# 0X_-_CPU_-_DISP_CSI.net
KiCad netlist of a schematic drawn in Altium Designer
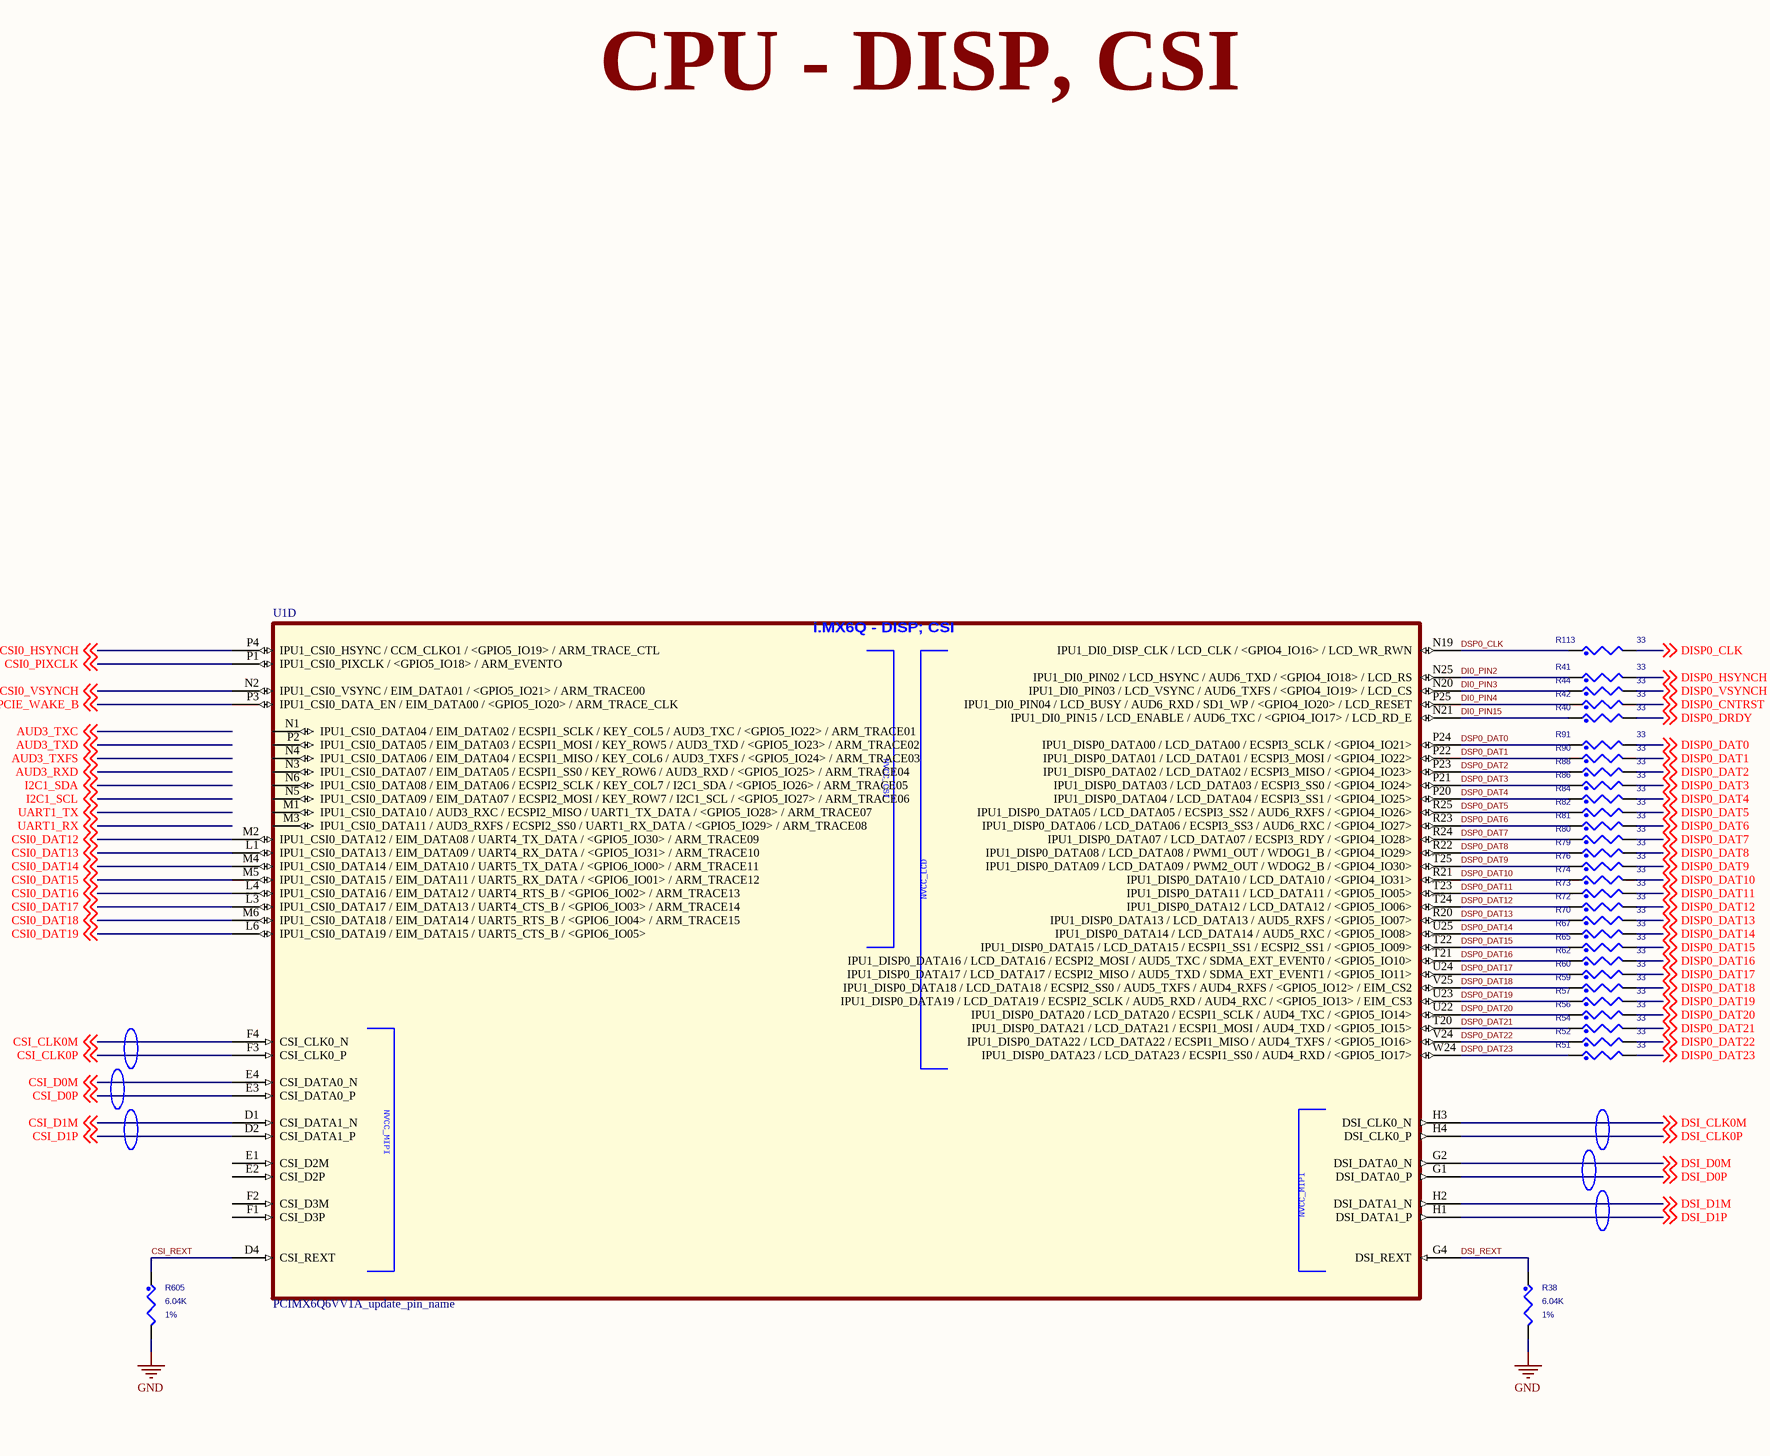
[diagram p0: [0X] - CPU - DISP, CSI.SchDoc, left]
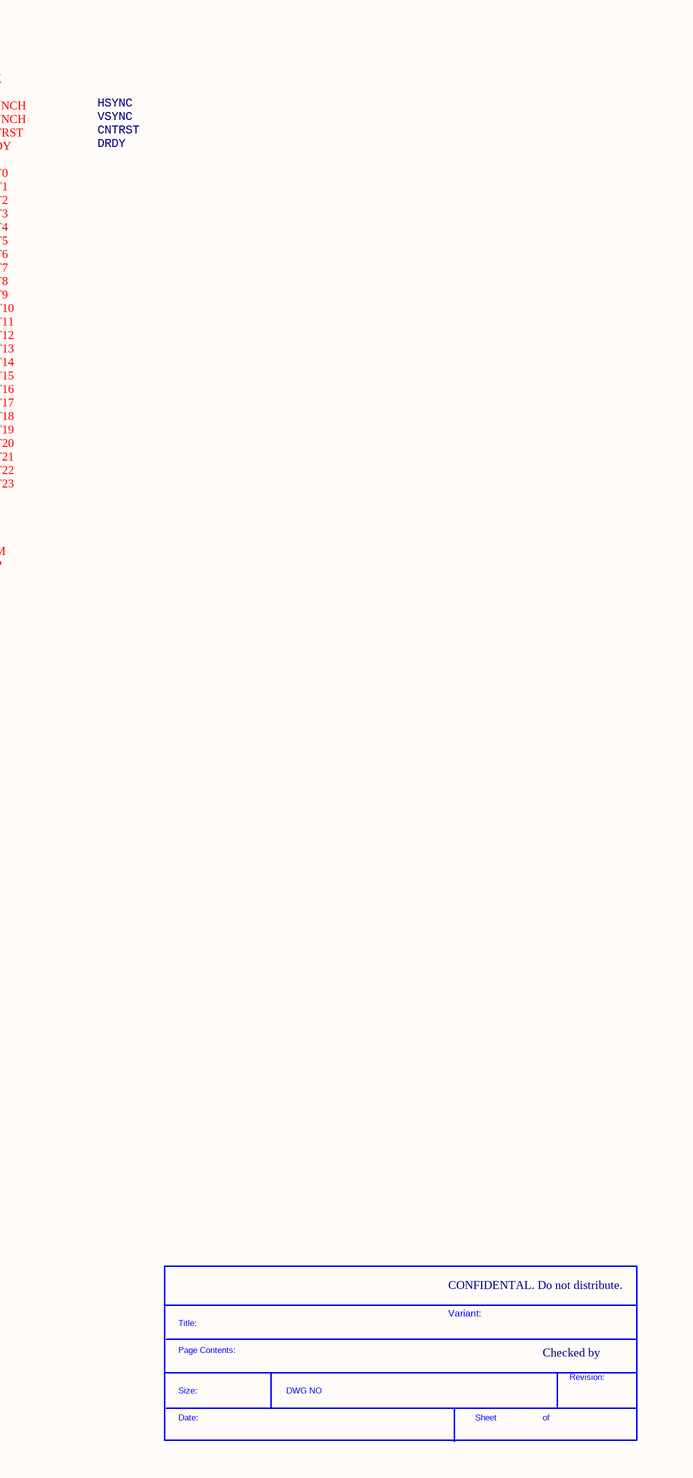
[diagram p1: [0X] - CPU - DISP, CSI.SchDoc, right]

(export (version "E")
  (design (tool "Eeschema 10.0.6"))
  (components
    (comp (ref "*") (value "SDTitleBlock") (libsource (lib "*") (part "SDTitleBlock")))
    (comp (ref "R38")
      (value "6.04K")
      (description "RES MF 6.04K  1/16W 1% 0402")
      (fields (field (name "TOLERANCE") "1%"))
      (libsource (lib "*") (part "RES"))
    )
    (comp (ref "R40")
      (value "33")
      (description "RES MF 33 OHM 1/16W 5% 0402")
      (fields (field (name "TOLERANCE") "5%"))
      (libsource (lib "*") (part "RES"))
    )
    (comp (ref "R41")
      (value "33")
      (description "RES MF 33 OHM 1/16W 5% 0402")
      (fields (field (name "TOLERANCE") "5%"))
      (libsource (lib "*") (part "RES"))
    )
    (comp (ref "R42")
      (value "33")
      (description "RES MF 33 OHM 1/16W 5% 0402")
      (fields (field (name "TOLERANCE") "5%"))
      (libsource (lib "*") (part "RES"))
    )
    (comp (ref "R44")
      (value "33")
      (description "RES MF 33 OHM 1/16W 5% 0402")
      (fields (field (name "TOLERANCE") "5%"))
      (libsource (lib "*") (part "RES"))
    )
    (comp (ref "R51")
      (value "33")
      (description "RES MF 33 OHM 1/16W 5% 0402")
      (fields (field (name "TOLERANCE") "5%"))
      (libsource (lib "*") (part "RES"))
    )
    (comp (ref "R52")
      (value "33")
      (description "RES MF 33 OHM 1/16W 5% 0402")
      (fields (field (name "TOLERANCE") "5%"))
      (libsource (lib "*") (part "RES"))
    )
    (comp (ref "R54")
      (value "33")
      (description "RES MF 33 OHM 1/16W 5% 0402")
      (fields (field (name "TOLERANCE") "5%"))
      (libsource (lib "*") (part "RES"))
    )
    (comp (ref "R56")
      (value "33")
      (description "RES MF 33 OHM 1/16W 5% 0402")
      (fields (field (name "TOLERANCE") "5%"))
      (libsource (lib "*") (part "RES"))
    )
    (comp (ref "R57")
      (value "33")
      (description "RES MF 33 OHM 1/16W 5% 0402")
      (fields (field (name "TOLERANCE") "5%"))
      (libsource (lib "*") (part "RES"))
    )
    (comp (ref "R59")
      (value "33")
      (description "RES MF 33 OHM 1/16W 5% 0402")
      (fields (field (name "TOLERANCE") "5%"))
      (libsource (lib "*") (part "RES"))
    )
    (comp (ref "R60")
      (value "33")
      (description "RES MF 33 OHM 1/16W 5% 0402")
      (fields (field (name "TOLERANCE") "5%"))
      (libsource (lib "*") (part "RES"))
    )
    (comp (ref "R62")
      (value "33")
      (description "RES MF 33 OHM 1/16W 5% 0402")
      (fields (field (name "TOLERANCE") "5%"))
      (libsource (lib "*") (part "RES"))
    )
    (comp (ref "R65")
      (value "33")
      (description "RES MF 33 OHM 1/16W 5% 0402")
      (fields (field (name "TOLERANCE") "5%"))
      (libsource (lib "*") (part "RES"))
    )
    (comp (ref "R67")
      (value "33")
      (description "RES MF 33 OHM 1/16W 5% 0402")
      (fields (field (name "TOLERANCE") "5%"))
      (libsource (lib "*") (part "RES"))
    )
    (comp (ref "R70")
      (value "33")
      (description "RES MF 33 OHM 1/16W 5% 0402")
      (fields (field (name "TOLERANCE") "5%"))
      (libsource (lib "*") (part "RES"))
    )
    (comp (ref "R72")
      (value "33")
      (description "RES MF 33 OHM 1/16W 5% 0402")
      (fields (field (name "TOLERANCE") "5%"))
      (libsource (lib "*") (part "RES"))
    )
    (comp (ref "R73")
      (value "33")
      (description "RES MF 33 OHM 1/16W 5% 0402")
      (fields (field (name "TOLERANCE") "5%"))
      (libsource (lib "*") (part "RES"))
    )
    (comp (ref "R74")
      (value "33")
      (description "RES MF 33 OHM 1/16W 5% 0402")
      (fields (field (name "TOLERANCE") "5%"))
      (libsource (lib "*") (part "RES"))
    )
    (comp (ref "R76")
      (value "33")
      (description "RES MF 33 OHM 1/16W 5% 0402")
      (fields (field (name "TOLERANCE") "5%"))
      (libsource (lib "*") (part "RES"))
    )
    (comp (ref "R79")
      (value "33")
      (description "RES MF 33 OHM 1/16W 5% 0402")
      (fields (field (name "TOLERANCE") "5%"))
      (libsource (lib "*") (part "RES"))
    )
    (comp (ref "R80")
      (value "33")
      (description "RES MF 33 OHM 1/16W 5% 0402")
      (fields (field (name "TOLERANCE") "5%"))
      (libsource (lib "*") (part "RES"))
    )
    (comp (ref "R81")
      (value "33")
      (description "RES MF 33 OHM 1/16W 5% 0402")
      (fields (field (name "TOLERANCE") "5%"))
      (libsource (lib "*") (part "RES"))
    )
    (comp (ref "R82")
      (value "33")
      (description "RES MF 33 OHM 1/16W 5% 0402")
      (fields (field (name "TOLERANCE") "5%"))
      (libsource (lib "*") (part "RES"))
    )
    (comp (ref "R84")
      (value "33")
      (description "RES MF 33 OHM 1/16W 5% 0402")
      (fields (field (name "TOLERANCE") "5%"))
      (libsource (lib "*") (part "RES"))
    )
    (comp (ref "R86")
      (value "33")
      (description "RES MF 33 OHM 1/16W 5% 0402")
      (fields (field (name "TOLERANCE") "5%"))
      (libsource (lib "*") (part "RES"))
    )
    (comp (ref "R88")
      (value "33")
      (description "RES MF 33 OHM 1/16W 5% 0402")
      (fields (field (name "TOLERANCE") "5%"))
      (libsource (lib "*") (part "RES"))
    )
    (comp (ref "R90")
      (value "33")
      (description "RES MF 33 OHM 1/16W 5% 0402")
      (fields (field (name "TOLERANCE") "5%"))
      (libsource (lib "*") (part "RES"))
    )
    (comp (ref "R91")
      (value "33")
      (description "RES MF 33 OHM 1/16W 5% 0402")
      (fields (field (name "TOLERANCE") "5%"))
      (libsource (lib "*") (part "RES"))
    )
    (comp (ref "R113")
      (value "33")
      (description "RES MF 33 OHM 1/16W 5% 0402")
      (fields (field (name "TOLERANCE") "5%"))
      (libsource (lib "*") (part "RES"))
    )
    (comp (ref "R605")
      (value "6.04K")
      (description "RES MF 6.04K  1/16W 1% 0402")
      (fields (field (name "TOLERANCE") "1%"))
      (libsource (lib "*") (part "RES"))
    )
    (comp (ref "U1")
      (value "PCIMX6Q6VV1A_update_pin_name")
      (libsource (lib "SCH-27516_C3_16_2_Library") (part "PCIMX6Q6VV1A_update_pin_name"))
    )
  )
  (nets
    (net (code "1") (name "/CSI_REXT") (class "Default")
      (node (ref "R605") (pin "1") (pinfunction "1_1") (pintype "passive"))
      (node (ref "U1") (pin "D4") (pinfunction "CSI_REXT_D4") (pintype "input"))
    )
    (net (code "2") (name "/DI0_PIN2") (class "Default")
      (node (ref "R41") (pin "1") (pinfunction "1_1") (pintype "passive"))
      (node (ref "U1") (pin "N25") (pinfunction "IPU1_DI0_PIN02_/_LCD_HSYNC_/_AUD6_TXD_/_<GPIO4_IO18>_/_LCD_RS_N25") (pintype "bidirectional"))
    )
    (net (code "3") (name "/DI0_PIN3") (class "Default")
      (node (ref "R44") (pin "1") (pinfunction "1_1") (pintype "passive"))
      (node (ref "U1") (pin "N20") (pinfunction "IPU1_DI0_PIN03_/_LCD_VSYNC_/_AUD6_TXFS_/_<GPIO4_IO19>_/_LCD_CS_N20") (pintype "bidirectional"))
    )
    (net (code "4") (name "/DI0_PIN4") (class "Default")
      (node (ref "R42") (pin "1") (pinfunction "1_1") (pintype "passive"))
      (node (ref "U1") (pin "P25") (pinfunction "IPU1_DI0_PIN04_/_LCD_BUSY_/_AUD6_RXD_/_SD1_WP_/_<GPIO4_IO20>_/_LCD_RESET_P25") (pintype "bidirectional"))
    )
    (net (code "5") (name "/DI0_PIN15") (class "Default")
      (node (ref "R40") (pin "1") (pinfunction "1_1") (pintype "passive"))
      (node (ref "U1") (pin "N21") (pinfunction "IPU1_DI0_PIN15_/_LCD_ENABLE_/_AUD6_TXC_/_<GPIO4_IO17>_/_LCD_RD_E_N21") (pintype "bidirectional"))
    )
    (net (code "6") (name "/DSI_REXT") (class "Default")
      (node (ref "R38") (pin "1") (pinfunction "1_1") (pintype "passive"))
      (node (ref "U1") (pin "G4") (pinfunction "DSI_REXT_G4") (pintype "input"))
    )
    (net (code "7") (name "/DSP0_CLK") (class "Default")
      (node (ref "R113") (pin "1") (pinfunction "1_1") (pintype "passive"))
      (node (ref "U1") (pin "N19") (pinfunction "IPU1_DI0_DISP_CLK_/_LCD_CLK_/_<GPIO4_IO16>_/_LCD_WR_RWN_N19") (pintype "bidirectional"))
    )
    (net (code "8") (name "/DSP0_DAT0") (class "Default")
      (node (ref "R91") (pin "1") (pinfunction "1_1") (pintype "passive"))
      (node (ref "U1") (pin "P24") (pinfunction "IPU1_DISP0_DATA00_/_LCD_DATA00_/_ECSPI3_SCLK_/_<GPIO4_IO21>_P24") (pintype "bidirectional"))
    )
    (net (code "9") (name "/DSP0_DAT1") (class "Default")
      (node (ref "R90") (pin "1") (pinfunction "1_1") (pintype "passive"))
      (node (ref "U1") (pin "P22") (pinfunction "IPU1_DISP0_DATA01_/_LCD_DATA01_/_ECSPI3_MOSI_/_<GPIO4_IO22>_P22") (pintype "bidirectional"))
    )
    (net (code "10") (name "/DSP0_DAT2") (class "Default")
      (node (ref "R88") (pin "1") (pinfunction "1_1") (pintype "passive"))
      (node (ref "U1") (pin "P23") (pinfunction "IPU1_DISP0_DATA02_/_LCD_DATA02_/_ECSPI3_MISO_/_<GPIO4_IO23>_P23") (pintype "bidirectional"))
    )
    (net (code "11") (name "/DSP0_DAT3") (class "Default")
      (node (ref "R86") (pin "1") (pinfunction "1_1") (pintype "passive"))
      (node (ref "U1") (pin "P21") (pinfunction "IPU1_DISP0_DATA03_/_LCD_DATA03_/_ECSPI3_SS0_/_<GPIO4_IO24>_P21") (pintype "bidirectional"))
    )
    (net (code "12") (name "/DSP0_DAT4") (class "Default")
      (node (ref "R84") (pin "1") (pinfunction "1_1") (pintype "passive"))
      (node (ref "U1") (pin "P20") (pinfunction "IPU1_DISP0_DATA04_/_LCD_DATA04_/_ECSPI3_SS1_/_<GPIO4_IO25>_P20") (pintype "bidirectional"))
    )
    (net (code "13") (name "/DSP0_DAT5") (class "Default")
      (node (ref "R82") (pin "1") (pinfunction "1_1") (pintype "passive"))
      (node (ref "U1") (pin "R25") (pinfunction "IPU1_DISP0_DATA05_/_LCD_DATA05_/_ECSPI3_SS2_/_AUD6_RXFS_/_<GPIO4_IO26>_R25") (pintype "bidirectional"))
    )
    (net (code "14") (name "/DSP0_DAT6") (class "Default")
      (node (ref "R81") (pin "1") (pinfunction "1_1") (pintype "passive"))
      (node (ref "U1") (pin "R23") (pinfunction "IPU1_DISP0_DATA06_/_LCD_DATA06_/_ECSPI3_SS3_/_AUD6_RXC_/_<GPIO4_IO27>_R23") (pintype "bidirectional"))
    )
    (net (code "15") (name "/DSP0_DAT7") (class "Default")
      (node (ref "R80") (pin "1") (pinfunction "1_1") (pintype "passive"))
      (node (ref "U1") (pin "R24") (pinfunction "IPU1_DISP0_DATA07_/_LCD_DATA07_/_ECSPI3_RDY_/_<GPIO4_IO28>_R24") (pintype "bidirectional"))
    )
    (net (code "16") (name "/DSP0_DAT8") (class "Default")
      (node (ref "R79") (pin "1") (pinfunction "1_1") (pintype "passive"))
      (node (ref "U1") (pin "R22") (pinfunction "IPU1_DISP0_DATA08_/_LCD_DATA08_/_PWM1_OUT_/_WDOG1_B_/_<GPIO4_IO29>_R22") (pintype "bidirectional"))
    )
    (net (code "17") (name "/DSP0_DAT9") (class "Default")
      (node (ref "R76") (pin "1") (pinfunction "1_1") (pintype "passive"))
      (node (ref "U1") (pin "T25") (pinfunction "IPU1_DISP0_DATA09_/_LCD_DATA09_/_PWM2_OUT_/_WDOG2_B_/_<GPIO4_IO30>_T25") (pintype "bidirectional"))
    )
    (net (code "18") (name "/DSP0_DAT10") (class "Default")
      (node (ref "R74") (pin "1") (pinfunction "1_1") (pintype "passive"))
      (node (ref "U1") (pin "R21") (pinfunction "IPU1_DISP0_DATA10_/_LCD_DATA10_/_<GPIO4_IO31>_R21") (pintype "bidirectional"))
    )
    (net (code "19") (name "/DSP0_DAT11") (class "Default")
      (node (ref "R73") (pin "1") (pinfunction "1_1") (pintype "passive"))
      (node (ref "U1") (pin "T23") (pinfunction "IPU1_DISP0_DATA11_/_LCD_DATA11_/_<GPIO5_IO05>_T23") (pintype "bidirectional"))
    )
    (net (code "20") (name "/DSP0_DAT12") (class "Default")
      (node (ref "R72") (pin "1") (pinfunction "1_1") (pintype "passive"))
      (node (ref "U1") (pin "T24") (pinfunction "IPU1_DISP0_DATA12_/_LCD_DATA12_/_<GPIO5_IO06>_T24") (pintype "bidirectional"))
    )
    (net (code "21") (name "/DSP0_DAT13") (class "Default")
      (node (ref "R70") (pin "1") (pinfunction "1_1") (pintype "passive"))
      (node (ref "U1") (pin "R20") (pinfunction "IPU1_DISP0_DATA13_/_LCD_DATA13_/_AUD5_RXFS_/_<GPIO5_IO07>_R20") (pintype "bidirectional"))
    )
    (net (code "22") (name "/DSP0_DAT14") (class "Default")
      (node (ref "R67") (pin "1") (pinfunction "1_1") (pintype "passive"))
      (node (ref "U1") (pin "U25") (pinfunction "IPU1_DISP0_DATA14_/_LCD_DATA14_/_AUD5_RXC_/_<GPIO5_IO08>_U25") (pintype "bidirectional"))
    )
    (net (code "23") (name "/DSP0_DAT15") (class "Default")
      (node (ref "R65") (pin "1") (pinfunction "1_1") (pintype "passive"))
      (node (ref "U1") (pin "T22") (pinfunction "IPU1_DISP0_DATA15_/_LCD_DATA15_/_ECSPI1_SS1_/_ECSPI2_SS1_/_<GPIO5_IO09>_T22") (pintype "bidirectional"))
    )
    (net (code "24") (name "/DSP0_DAT16") (class "Default")
      (node (ref "R62") (pin "1") (pinfunction "1_1") (pintype "passive"))
      (node (ref "U1") (pin "T21") (pinfunction "IPU1_DISP0_DATA16_/_LCD_DATA16_/_ECSPI2_MOSI_/_AUD5_TXC_/_SDMA_EXT_EVENT0_/_<GPIO5_IO10>_T21") (pintype "bidirectional"))
    )
    (net (code "25") (name "/DSP0_DAT17") (class "Default")
      (node (ref "R60") (pin "1") (pinfunction "1_1") (pintype "passive"))
      (node (ref "U1") (pin "U24") (pinfunction "IPU1_DISP0_DATA17_/_LCD_DATA17_/_ECSPI2_MISO_/_AUD5_TXD_/_SDMA_EXT_EVENT1_/_<GPIO5_IO11>_U24") (pintype "bidirectional"))
    )
    (net (code "26") (name "/DSP0_DAT18") (class "Default")
      (node (ref "R59") (pin "1") (pinfunction "1_1") (pintype "passive"))
      (node (ref "U1") (pin "V25") (pinfunction "IPU1_DISP0_DATA18_/_LCD_DATA18_/_ECSPI2_SS0_/_AUD5_TXFS_/_AUD4_RXFS_/_<GPIO5_IO12>_/_EIM_CS2_V25") (pintype "bidirectional"))
    )
    (net (code "27") (name "/DSP0_DAT19") (class "Default")
      (node (ref "R57") (pin "1") (pinfunction "1_1") (pintype "passive"))
      (node (ref "U1") (pin "U23") (pinfunction "IPU1_DISP0_DATA19_/_LCD_DATA19_/_ECSPI2_SCLK_/_AUD5_RXD_/_AUD4_RXC_/_<GPIO5_IO13>_/_EIM_CS3_U23") (pintype "bidirectional"))
    )
    (net (code "28") (name "/DSP0_DAT20") (class "Default")
      (node (ref "R56") (pin "1") (pinfunction "1_1") (pintype "passive"))
      (node (ref "U1") (pin "U22") (pinfunction "IPU1_DISP0_DATA20_/_LCD_DATA20_/_ECSPI1_SCLK_/_AUD4_TXC_/_<GPIO5_IO14>_U22") (pintype "bidirectional"))
    )
    (net (code "29") (name "/DSP0_DAT21") (class "Default")
      (node (ref "R54") (pin "1") (pinfunction "1_1") (pintype "passive"))
      (node (ref "U1") (pin "T20") (pinfunction "IPU1_DISP0_DATA21_/_LCD_DATA21_/_ECSPI1_MOSI_/_AUD4_TXD_/_<GPIO5_IO15>_T20") (pintype "bidirectional"))
    )
    (net (code "30") (name "/DSP0_DAT22") (class "Default")
      (node (ref "R52") (pin "1") (pinfunction "1_1") (pintype "passive"))
      (node (ref "U1") (pin "V24") (pinfunction "IPU1_DISP0_DATA22_/_LCD_DATA22_/_ECSPI1_MISO_/_AUD4_TXFS_/_<GPIO5_IO16>_V24") (pintype "bidirectional"))
    )
    (net (code "31") (name "/DSP0_DAT23") (class "Default")
      (node (ref "R51") (pin "1") (pinfunction "1_1") (pintype "passive"))
      (node (ref "U1") (pin "W24") (pinfunction "IPU1_DISP0_DATA23_/_LCD_DATA23_/_ECSPI1_SS0_/_AUD4_RXD_/_<GPIO5_IO17>_W24") (pintype "bidirectional"))
    )
    (net (code "36") (name "CSI0_DAT12") (class "Default")
      (node (ref "U1") (pin "M2") (pinfunction "IPU1_CSI0_DATA12_/_EIM_DATA08_/_UART4_TX_DATA_/_<GPIO5_IO30>_/_ARM_TRACE09_M2") (pintype "bidirectional"))
    )
    (net (code "37") (name "CSI0_DAT13") (class "Default")
      (node (ref "U1") (pin "L1") (pinfunction "IPU1_CSI0_DATA13_/_EIM_DATA09_/_UART4_RX_DATA_/_<GPIO5_IO31>_/_ARM_TRACE10_L1") (pintype "bidirectional"))
    )
    (net (code "38") (name "CSI0_DAT14") (class "Default")
      (node (ref "U1") (pin "M4") (pinfunction "IPU1_CSI0_DATA14_/_EIM_DATA10_/_UART5_TX_DATA_/_<GPIO6_IO00>_/_ARM_TRACE11_M4") (pintype "bidirectional"))
    )
    (net (code "39") (name "CSI0_DAT15") (class "Default")
      (node (ref "U1") (pin "M5") (pinfunction "IPU1_CSI0_DATA15_/_EIM_DATA11_/_UART5_RX_DATA_/_<GPIO6_IO01>_/_ARM_TRACE12_M5") (pintype "bidirectional"))
    )
    (net (code "40") (name "CSI0_DAT16") (class "Default")
      (node (ref "U1") (pin "L4") (pinfunction "IPU1_CSI0_DATA16_/_EIM_DATA12_/_UART4_RTS_B_/_<GPIO6_IO02>_/_ARM_TRACE13_L4") (pintype "bidirectional"))
    )
    (net (code "41") (name "CSI0_DAT17") (class "Default")
      (node (ref "U1") (pin "L3") (pinfunction "IPU1_CSI0_DATA17_/_EIM_DATA13_/_UART4_CTS_B_/_<GPIO6_IO03>_/_ARM_TRACE14_L3") (pintype "bidirectional"))
    )
    (net (code "42") (name "CSI0_DAT18") (class "Default")
      (node (ref "U1") (pin "M6") (pinfunction "IPU1_CSI0_DATA18_/_EIM_DATA14_/_UART5_RTS_B_/_<GPIO6_IO04>_/_ARM_TRACE15_M6") (pintype "bidirectional"))
    )
    (net (code "43") (name "CSI0_DAT19") (class "Default")
      (node (ref "U1") (pin "L6") (pinfunction "IPU1_CSI0_DATA19_/_EIM_DATA15_/_UART5_CTS_B_/_<GPIO6_IO05>_L6") (pintype "bidirectional"))
    )
    (net (code "44") (name "CSI0_HSYNCH") (class "Default")
      (node (ref "U1") (pin "P4") (pinfunction "IPU1_CSI0_HSYNC_/_CCM_CLKO1_/_<GPIO5_IO19>_/_ARM_TRACE_CTL_P4") (pintype "bidirectional"))
    )
    (net (code "45") (name "CSI0_PIXCLK") (class "Default")
      (node (ref "U1") (pin "P1") (pinfunction "IPU1_CSI0_PIXCLK_/_<GPIO5_IO18>_/_ARM_EVENTO_P1") (pintype "bidirectional"))
    )
    (net (code "46") (name "CSI0_VSYNCH") (class "Default")
      (node (ref "U1") (pin "N2") (pinfunction "IPU1_CSI0_VSYNC_/_EIM_DATA01_/_<GPIO5_IO21>_/_ARM_TRACE00_N2") (pintype "bidirectional"))
    )
    (net (code "47") (name "CSI_CLK0M") (class "Default")
      (node (ref "U1") (pin "F4") (pinfunction "CSI_CLK0_N_F4") (pintype "input"))
    )
    (net (code "48") (name "CSI_CLK0P") (class "Default")
      (node (ref "U1") (pin "F3") (pinfunction "CSI_CLK0_P_F3") (pintype "input"))
    )
    (net (code "49") (name "CSI_D0M") (class "Default")
      (node (ref "U1") (pin "E4") (pinfunction "CSI_DATA0_N_E4") (pintype "input"))
    )
    (net (code "50") (name "CSI_D0P") (class "Default")
      (node (ref "U1") (pin "E3") (pinfunction "CSI_DATA0_P_E3") (pintype "input"))
    )
    (net (code "51") (name "CSI_D1M") (class "Default")
      (node (ref "U1") (pin "D1") (pinfunction "CSI_DATA1_N_D1") (pintype "input"))
    )
    (net (code "52") (name "CSI_D1P") (class "Default")
      (node (ref "U1") (pin "D2") (pinfunction "CSI_DATA1_P_D2") (pintype "input"))
    )
    (net (code "53") (name "DISP0_CLK") (class "Default")
      (node (ref "R113") (pin "2") (pinfunction "2_2") (pintype "passive"))
    )
    (net (code "54") (name "DISP0_CNTRST") (class "Default")
      (node (ref "R42") (pin "2") (pinfunction "2_2") (pintype "passive"))
    )
    (net (code "55") (name "DISP0_DAT0") (class "Default")
      (node (ref "R91") (pin "2") (pinfunction "2_2") (pintype "passive"))
    )
    (net (code "56") (name "DISP0_DAT1") (class "Default")
      (node (ref "R90") (pin "2") (pinfunction "2_2") (pintype "passive"))
    )
    (net (code "57") (name "DISP0_DAT2") (class "Default")
      (node (ref "R88") (pin "2") (pinfunction "2_2") (pintype "passive"))
    )
    (net (code "58") (name "DISP0_DAT3") (class "Default")
      (node (ref "R86") (pin "2") (pinfunction "2_2") (pintype "passive"))
    )
    (net (code "59") (name "DISP0_DAT4") (class "Default")
      (node (ref "R84") (pin "2") (pinfunction "2_2") (pintype "passive"))
    )
    (net (code "60") (name "DISP0_DAT5") (class "Default")
      (node (ref "R82") (pin "2") (pinfunction "2_2") (pintype "passive"))
    )
    (net (code "61") (name "DISP0_DAT6") (class "Default")
      (node (ref "R81") (pin "2") (pinfunction "2_2") (pintype "passive"))
    )
    (net (code "62") (name "DISP0_DAT7") (class "Default")
      (node (ref "R80") (pin "2") (pinfunction "2_2") (pintype "passive"))
    )
    (net (code "63") (name "DISP0_DAT8") (class "Default")
      (node (ref "R79") (pin "2") (pinfunction "2_2") (pintype "passive"))
    )
    (net (code "64") (name "DISP0_DAT9") (class "Default")
      (node (ref "R76") (pin "2") (pinfunction "2_2") (pintype "passive"))
    )
    (net (code "65") (name "DISP0_DAT10") (class "Default")
      (node (ref "R74") (pin "2") (pinfunction "2_2") (pintype "passive"))
    )
    (net (code "66") (name "DISP0_DAT11") (class "Default")
      (node (ref "R73") (pin "2") (pinfunction "2_2") (pintype "passive"))
    )
    (net (code "67") (name "DISP0_DAT12") (class "Default")
      (node (ref "R72") (pin "2") (pinfunction "2_2") (pintype "passive"))
    )
    (net (code "68") (name "DISP0_DAT13") (class "Default")
      (node (ref "R70") (pin "2") (pinfunction "2_2") (pintype "passive"))
    )
    (net (code "69") (name "DISP0_DAT14") (class "Default")
      (node (ref "R67") (pin "2") (pinfunction "2_2") (pintype "passive"))
    )
    (net (code "70") (name "DISP0_DAT15") (class "Default")
      (node (ref "R65") (pin "2") (pinfunction "2_2") (pintype "passive"))
    )
    (net (code "71") (name "DISP0_DAT16") (class "Default")
      (node (ref "R62") (pin "2") (pinfunction "2_2") (pintype "passive"))
    )
    (net (code "72") (name "DISP0_DAT17") (class "Default")
      (node (ref "R60") (pin "2") (pinfunction "2_2") (pintype "passive"))
    )
    (net (code "73") (name "DISP0_DAT18") (class "Default")
      (node (ref "R59") (pin "2") (pinfunction "2_2") (pintype "passive"))
    )
    (net (code "74") (name "DISP0_DAT19") (class "Default")
      (node (ref "R57") (pin "2") (pinfunction "2_2") (pintype "passive"))
    )
    (net (code "75") (name "DISP0_DAT20") (class "Default")
      (node (ref "R56") (pin "2") (pinfunction "2_2") (pintype "passive"))
    )
    (net (code "76") (name "DISP0_DAT21") (class "Default")
      (node (ref "R54") (pin "2") (pinfunction "2_2") (pintype "passive"))
    )
    (net (code "77") (name "DISP0_DAT22") (class "Default")
      (node (ref "R52") (pin "2") (pinfunction "2_2") (pintype "passive"))
    )
    (net (code "78") (name "DISP0_DAT23") (class "Default")
      (node (ref "R51") (pin "2") (pinfunction "2_2") (pintype "passive"))
    )
    (net (code "79") (name "DISP0_DRDY") (class "Default")
      (node (ref "R40") (pin "2") (pinfunction "2_2") (pintype "passive"))
    )
    (net (code "80") (name "DISP0_HSYNCH") (class "Default")
      (node (ref "R41") (pin "2") (pinfunction "2_2") (pintype "passive"))
    )
    (net (code "81") (name "DISP0_VSYNCH") (class "Default")
      (node (ref "R44") (pin "2") (pinfunction "2_2") (pintype "passive"))
    )
    (net (code "82") (name "DSI_CLK0M") (class "Default")
      (node (ref "U1") (pin "H3") (pinfunction "DSI_CLK0_N_H3") (pintype "output"))
    )
    (net (code "83") (name "DSI_CLK0P") (class "Default")
      (node (ref "U1") (pin "H4") (pinfunction "DSI_CLK0_P_H4") (pintype "output"))
    )
    (net (code "84") (name "DSI_D0M") (class "Default")
      (node (ref "U1") (pin "G2") (pinfunction "DSI_DATA0_N_G2") (pintype "output"))
    )
    (net (code "85") (name "DSI_D0P") (class "Default")
      (node (ref "U1") (pin "G1") (pinfunction "DSI_DATA0_P_G1") (pintype "output"))
    )
    (net (code "86") (name "DSI_D1M") (class "Default")
      (node (ref "U1") (pin "H2") (pinfunction "DSI_DATA1_N_H2") (pintype "output"))
    )
    (net (code "87") (name "DSI_D1P") (class "Default")
      (node (ref "U1") (pin "H1") (pinfunction "DSI_DATA1_P_H1") (pintype "output"))
    )
    (net (code "88") (name "GND") (class "Default")
      (node (ref "R38") (pin "2") (pinfunction "2_2") (pintype "passive"))
      (node (ref "R605") (pin "2") (pinfunction "2_2") (pintype "passive"))
    )
    (net (code "91") (name "PCIE_WAKE_B") (class "Default")
      (node (ref "U1") (pin "P3") (pinfunction "IPU1_CSI0_DATA_EN_/_EIM_DATA00_/_<GPIO5_IO20>_/_ARM_TRACE_CLK_P3") (pintype "bidirectional"))
    )
    (net (code "94") (name "unconnected-(U1D-CSI_D2M-PadE1)") (class "Default")
      (node (ref "U1") (pin "E1") (pinfunction "CSI_D2M_E1") (pintype "input"))
    )
    (net (code "95") (name "unconnected-(U1D-CSI_D2P-PadE2)") (class "Default")
      (node (ref "U1") (pin "E2") (pinfunction "CSI_D2P_E2") (pintype "input"))
    )
    (net (code "96") (name "unconnected-(U1D-CSI_D3M-PadF2)") (class "Default")
      (node (ref "U1") (pin "F2") (pinfunction "CSI_D3M_F2") (pintype "input"))
    )
    (net (code "97") (name "unconnected-(U1D-CSI_D3P-PadF1)") (class "Default")
      (node (ref "U1") (pin "F1") (pinfunction "CSI_D3P_F1") (pintype "input"))
    )
    (net (code "98") (name "unconnected-(U1D-IPU1_CSI0_DATA04_{slash}_EIM_DATA02_{slash}_ECSPI1_SCLK_{slash}_KEY_COL5_{slash}_AUD3_TXC_{slash}_<GPIO5_IO22>_{slash}_ARM_TRACE01-PadN1)") (class "Default")
      (node (ref "U1") (pin "N1") (pinfunction "IPU1_CSI0_DATA04_/_EIM_DATA02_/_ECSPI1_SCLK_/_KEY_COL5_/_AUD3_TXC_/_<GPIO5_IO22>_/_ARM_TRACE01_N1") (pintype "bidirectional"))
    )
    (net (code "99") (name "unconnected-(U1D-IPU1_CSI0_DATA05_{slash}_EIM_DATA03_{slash}_ECSPI1_MOSI_{slash}_KEY_ROW5_{slash}_AUD3_TXD_{slash}_<GPIO5_IO23>_{slash}_ARM_TRACE02-PadP2)") (class "Default")
      (node (ref "U1") (pin "P2") (pinfunction "IPU1_CSI0_DATA05_/_EIM_DATA03_/_ECSPI1_MOSI_/_KEY_ROW5_/_AUD3_TXD_/_<GPIO5_IO23>_/_ARM_TRACE02_P2") (pintype "bidirectional"))
    )
    (net (code "100") (name "unconnected-(U1D-IPU1_CSI0_DATA06_{slash}_EIM_DATA04_{slash}_ECSPI1_MISO_{slash}_KEY_COL6_{slash}_AUD3_TXFS_{slash}_<GPIO5_IO24>_{slash}_ARM_TRACE03-PadN4)") (class "Default")
      (node (ref "U1") (pin "N4") (pinfunction "IPU1_CSI0_DATA06_/_EIM_DATA04_/_ECSPI1_MISO_/_KEY_COL6_/_AUD3_TXFS_/_<GPIO5_IO24>_/_ARM_TRACE03_N4") (pintype "bidirectional"))
    )
    (net (code "101") (name "unconnected-(U1D-IPU1_CSI0_DATA07_{slash}_EIM_DATA05_{slash}_ECSPI1_SS0_{slash}_KEY_ROW6_{slash}_AUD3_RXD_{slash}_<GPIO5_IO25>_{slash}_ARM_TRACE04-PadN3)") (class "Default")
      (node (ref "U1") (pin "N3") (pinfunction "IPU1_CSI0_DATA07_/_EIM_DATA05_/_ECSPI1_SS0_/_KEY_ROW6_/_AUD3_RXD_/_<GPIO5_IO25>_/_ARM_TRACE04_N3") (pintype "bidirectional"))
    )
    (net (code "102") (name "unconnected-(U1D-IPU1_CSI0_DATA08_{slash}_EIM_DATA06_{slash}_ECSPI2_SCLK_{slash}_KEY_COL7_{slash}_I2C1_SDA_{slash}_<GPIO5_IO26>_{slash}_ARM_TRACE05-PadN6)") (class "Default")
      (node (ref "U1") (pin "N6") (pinfunction "IPU1_CSI0_DATA08_/_EIM_DATA06_/_ECSPI2_SCLK_/_KEY_COL7_/_I2C1_SDA_/_<GPIO5_IO26>_/_ARM_TRACE05_N6") (pintype "bidirectional"))
    )
    (net (code "103") (name "unconnected-(U1D-IPU1_CSI0_DATA09_{slash}_EIM_DATA07_{slash}_ECSPI2_MOSI_{slash}_KEY_ROW7_{slash}_I2C1_SCL_{slash}_<GPIO5_IO27>_{slash}_ARM_TRACE06-PadN5)") (class "Default")
      (node (ref "U1") (pin "N5") (pinfunction "IPU1_CSI0_DATA09_/_EIM_DATA07_/_ECSPI2_MOSI_/_KEY_ROW7_/_I2C1_SCL_/_<GPIO5_IO27>_/_ARM_TRACE06_N5") (pintype "bidirectional"))
    )
    (net (code "104") (name "unconnected-(U1D-IPU1_CSI0_DATA10_{slash}_AUD3_RXC_{slash}_ECSPI2_MISO_{slash}_UART1_TX_DATA_{slash}_<GPIO5_IO28>_{slash}_ARM_TRACE07-PadM1)") (class "Default")
      (node (ref "U1") (pin "M1") (pinfunction "IPU1_CSI0_DATA10_/_AUD3_RXC_/_ECSPI2_MISO_/_UART1_TX_DATA_/_<GPIO5_IO28>_/_ARM_TRACE07_M1") (pintype "bidirectional"))
    )
    (net (code "105") (name "unconnected-(U1D-IPU1_CSI0_DATA11_{slash}_AUD3_RXFS_{slash}_ECSPI2_SS0_{slash}_UART1_RX_DATA_{slash}_<GPIO5_IO29>_{slash}_ARM_TRACE08-PadM3)") (class "Default")
      (node (ref "U1") (pin "M3") (pinfunction "IPU1_CSI0_DATA11_/_AUD3_RXFS_/_ECSPI2_SS0_/_UART1_RX_DATA_/_<GPIO5_IO29>_/_ARM_TRACE08_M3") (pintype "bidirectional"))
    )
  )
)
